# Blinky.net
KiCad netlist of a schematic drawn in EAGLE
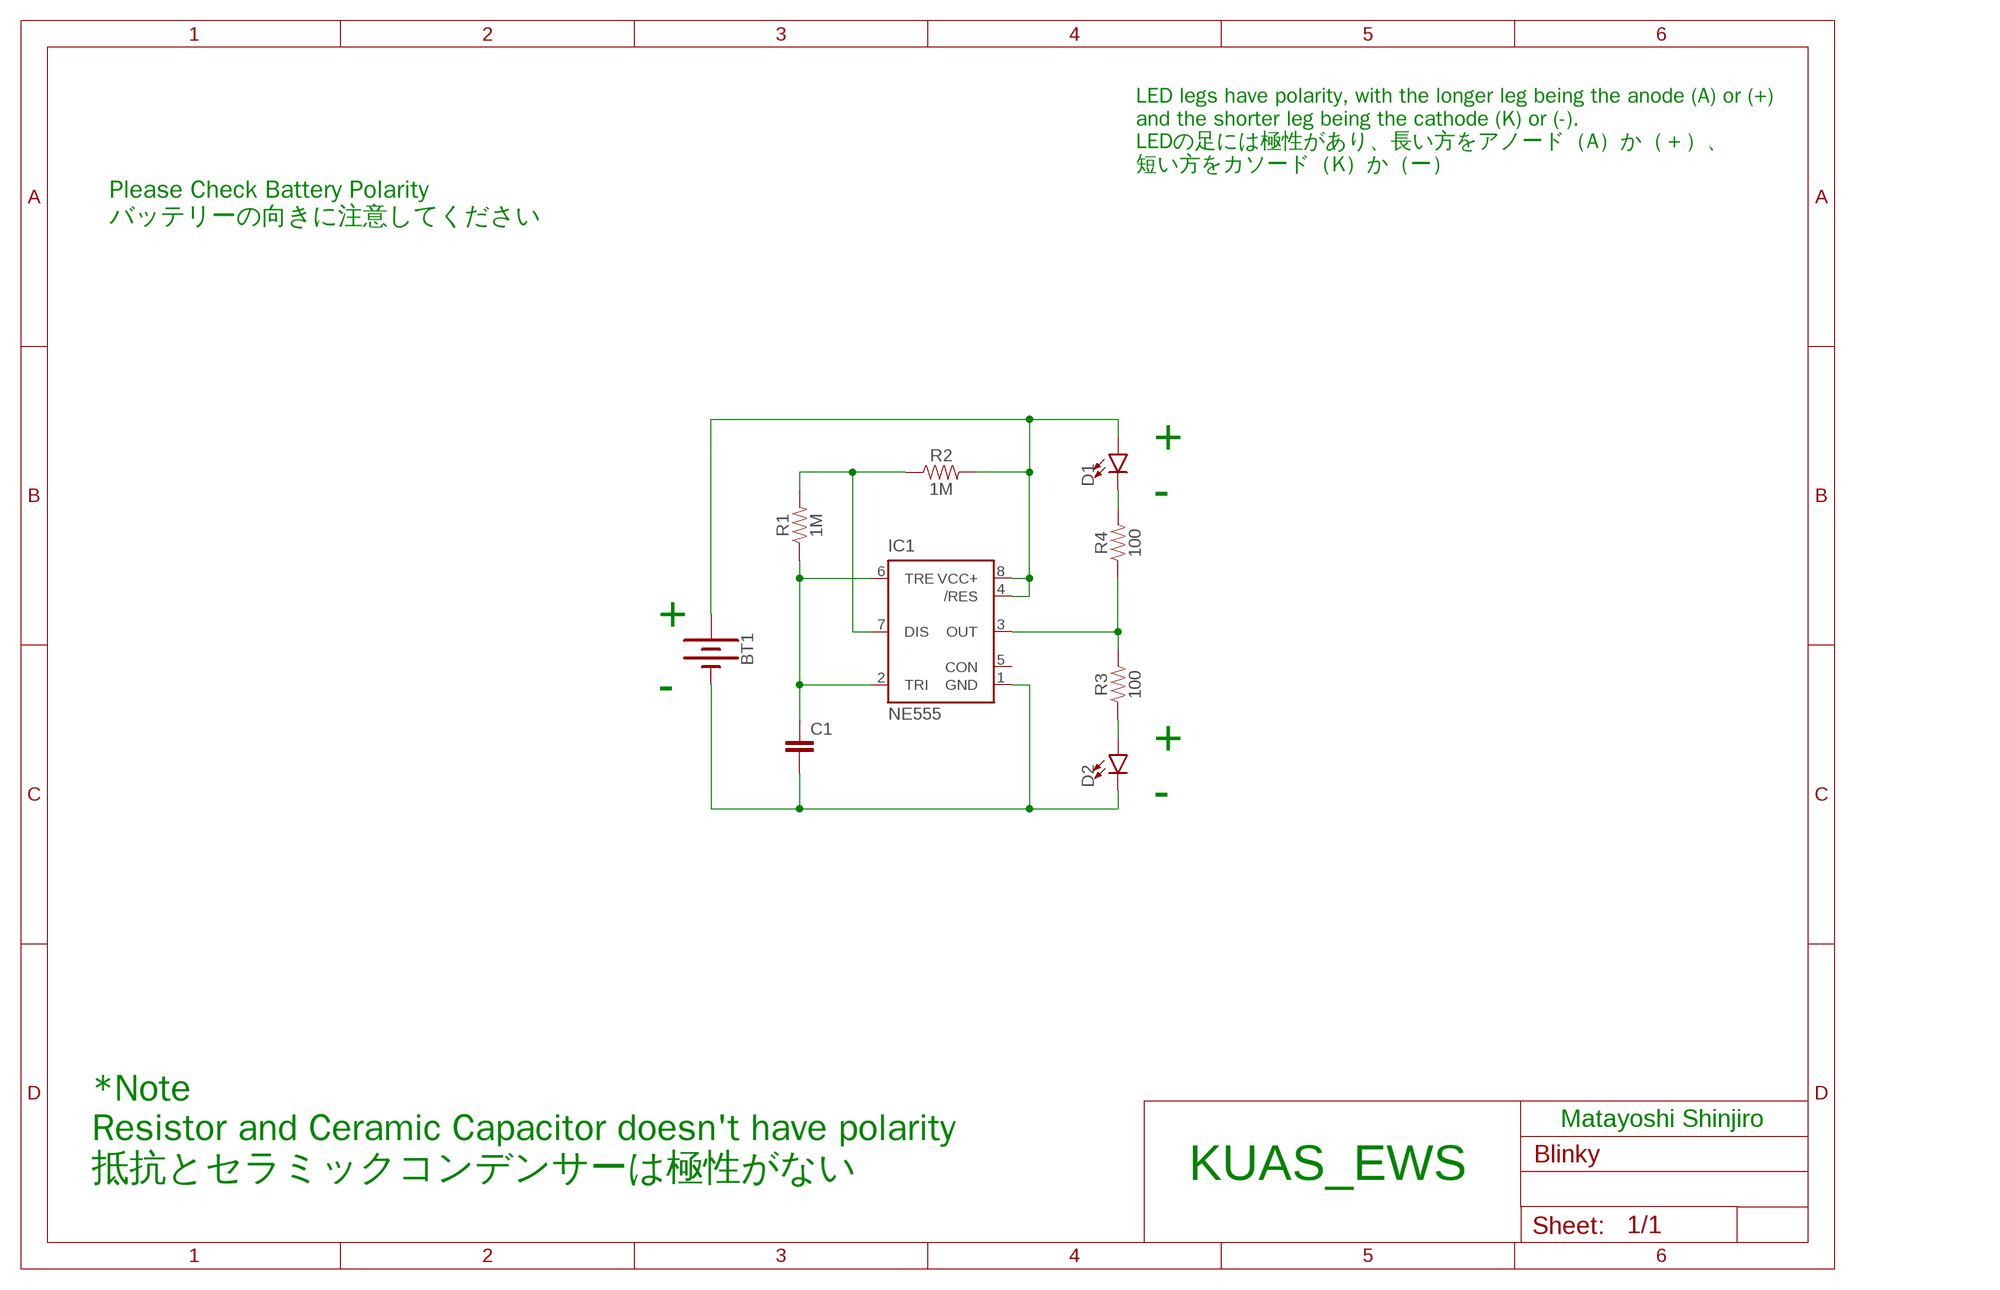
[diagram p0: schematic, sheet 1]

(export (version "E")
  (design (tool "Eeschema 10.0.6"))
  (components
    (comp (ref "BT1")
      (value "BATTERY-AA")
      (footprint "eagle-import:BATTERY-AA")
      (libsource (lib "eagle-import") (part "BATTERY-AA"))
    )
    (comp (ref "C1")
      (value "C-EU025-025X050")
      (footprint "eagle-import:C025-025X050")
      (libsource (lib "eagle-import") (part "C-EU025-025X050"))
    )
    (comp (ref "D1")
      (value "LED5MM-KIT")
      (footprint "eagle-import:LED_5MM-KIT")
      (libsource (lib "eagle-import") (part "LED5MM-KIT"))
    )
    (comp (ref "D2")
      (value "LED5MM-KIT")
      (footprint "eagle-import:LED_5MM-KIT")
      (libsource (lib "eagle-import") (part "LED5MM-KIT"))
    )
    (comp (ref "IC1")
      (value "NE555")
      (footprint "eagle-import:DIL-08")
      (fields (field (name "MF") "Arrow Electronics") (field (name "MPN") "NE555N"))
      (libsource (lib "eagle-import") (part "NE555"))
    )
    (comp (ref "R1")
      (value "1M")
      (footprint "eagle-import:AXIAL-0.3")
      (libsource (lib "eagle-import") (part "1MOHM-HORIZ-1/6W-5%"))
    )
    (comp (ref "R2")
      (value "1M")
      (footprint "eagle-import:AXIAL-0.3")
      (libsource (lib "eagle-import") (part "1MOHM-HORIZ-1/6W-5%"))
    )
    (comp (ref "R3")
      (value "100")
      (footprint "eagle-import:AXIAL-0.3")
      (libsource (lib "eagle-import") (part "1MOHM-HORIZ-1/6W-5%"))
    )
    (comp (ref "R4")
      (value "100")
      (footprint "eagle-import:AXIAL-0.3")
      (libsource (lib "eagle-import") (part "1MOHM-HORIZ-1/6W-5%"))
    )
  )
  (nets
    (net (code "1") (name "Net-(BT1-+)") (class "Default")
      (node (ref "BT1") (pin "PWR@1") (pinfunction "+_PWR@1") (pintype "power_in"))
      (node (ref "D1") (pin "A") (pinfunction "A_A") (pintype "passive"))
      (node (ref "IC1") (pin "4") (pinfunction "/RES_4") (pintype "input"))
      (node (ref "IC1") (pin "8") (pinfunction "VCC+_8") (pintype "power_in"))
      (node (ref "R2") (pin "P$2") (pinfunction "2_P$2") (pintype "passive"))
    )
    (net (code "2") (name "Net-(BT1--)") (class "Default")
      (node (ref "BT1") (pin "GND@1") (pinfunction "-_GND@1") (pintype "power_in"))
      (node (ref "C1") (pin "2") (pinfunction "2_2") (pintype "passive"))
      (node (ref "D2") (pin "K") (pinfunction "C_K") (pintype "passive"))
      (node (ref "IC1") (pin "1") (pinfunction "GND_1") (pintype "power_in"))
    )
    (net (code "3") (name "Net-(D1-C)") (class "Default")
      (node (ref "D1") (pin "K") (pinfunction "C_K") (pintype "passive"))
      (node (ref "R4") (pin "P$2") (pinfunction "2_P$2") (pintype "passive"))
    )
    (net (code "4") (name "Net-(IC1-DIS)") (class "Default")
      (node (ref "IC1") (pin "7") (pinfunction "DIS_7") (pintype "input"))
      (node (ref "R1") (pin "P$2") (pinfunction "2_P$2") (pintype "passive"))
      (node (ref "R2") (pin "P$1") (pinfunction "1_P$1") (pintype "passive"))
    )
    (net (code "5") (name "Net-(IC1-OUT)") (class "Default")
      (node (ref "IC1") (pin "3") (pinfunction "OUT_3") (pintype "output"))
      (node (ref "R3") (pin "P$2") (pinfunction "2_P$2") (pintype "passive"))
      (node (ref "R4") (pin "P$1") (pinfunction "1_P$1") (pintype "passive"))
    )
    (net (code "6") (name "Net-(IC1-TRE)") (class "Default")
      (node (ref "C1") (pin "1") (pinfunction "1_1") (pintype "passive"))
      (node (ref "IC1") (pin "2") (pinfunction "TRI_2") (pintype "input"))
      (node (ref "IC1") (pin "6") (pinfunction "TRE_6") (pintype "input"))
      (node (ref "R1") (pin "P$1") (pinfunction "1_P$1") (pintype "passive"))
    )
    (net (code "7") (name "Net-(R3-1)") (class "Default")
      (node (ref "D2") (pin "A") (pinfunction "A_A") (pintype "passive"))
      (node (ref "R3") (pin "P$1") (pinfunction "1_P$1") (pintype "passive"))
    )
    (net (code "8") (name "unconnected-(IC1-CON-Pad5)") (class "Default")
      (node (ref "IC1") (pin "5") (pinfunction "CON_5") (pintype "input"))
    )
  )
)
